# Sheet1.net
KiCad netlist of a schematic drawn in Altium Designer
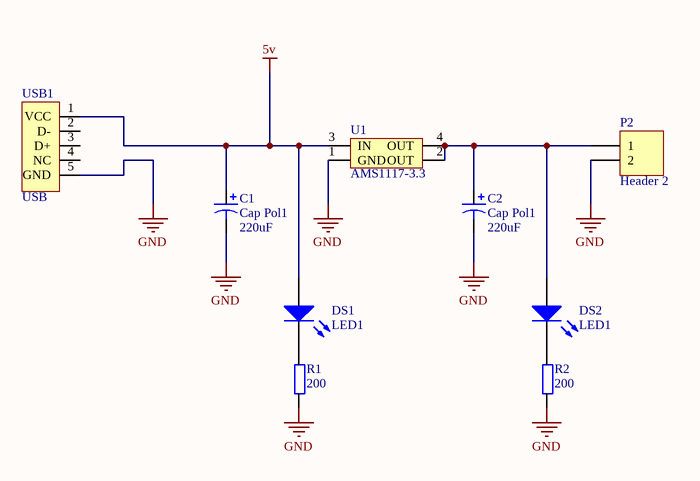
[diagram p0: Sheet1.SchDoc]

(export (version "E")
  (design (tool "Eeschema 10.0.6"))
  (components
    (comp (ref "C1")
      (value "Cap Pol1")
      (footprint "RB015-3:RB.15/.3")
      (description "Polarized Capacitor (Radial)")
      (fields (field (name "ALTIUM_VALUE") "220uF") (field (name "PUBLISHER") "Altium Limited"))
      (libsource (lib "Miscellaneous Devices") (part "Cap Pol1"))
    )
    (comp (ref "C2")
      (value "Cap Pol1")
      (footprint "RB015-3:RB.15/.3")
      (description "Polarized Capacitor (Radial)")
      (fields (field (name "ALTIUM_VALUE") "220uF") (field (name "PUBLISHER") "Altium Limited"))
      (libsource (lib "Miscellaneous Devices") (part "Cap Pol1"))
    )
    (comp (ref "DS1")
      (value "LED1")
      (footprint "LED0805:LED0805")
      (description "Typical RED, GREEN, YELLOW, AMBER GaAs LED")
      (fields (field (name "PUBLISHER") "Altium Limited"))
      (libsource (lib "WarShip V3 STM32103封装库") (part "LED2"))
    )
    (comp (ref "DS2")
      (value "LED1")
      (footprint "LED0805:LED0805")
      (description "Typical RED, GREEN, YELLOW, AMBER GaAs LED")
      (fields (field (name "PUBLISHER") "Altium Limited"))
      (libsource (lib "WarShip V3 STM32103封装库") (part "LED2"))
    )
    (comp (ref "P2")
      (value "Header 2")
      (footprint "HDR1X2")
      (description "Header, 2-Pin")
      (fields (field (name "PUBLISHER") "Altium Limited"))
      (libsource (lib "Miscellaneous Connectors") (part "Header 2"))
    )
    (comp (ref "R1") (value "200") (footprint "0805") (libsource (lib "WarShip V3 STM32103封装库") (part "R")))
    (comp (ref "R2") (value "200") (footprint "0805") (libsource (lib "WarShip V3 STM32103封装库") (part "R")))
    (comp (ref "U1")
      (value "AMS1117-3.3")
      (footprint "AMS1117")
      (libsource (lib "WarShip V3 STM32103封装库") (part "AMS1117"))
    )
    (comp (ref "USB1")
      (value "USB")
      (footprint "DIP-2p")
      (libsource (lib "WarShip V3 STM32103封装库") (part "USB5"))
    )
  )
  (nets
    (net (code "1") (name "5v") (class "Default")
      (node (ref "C1") (pin "1") (pinfunction "1_1") (pintype "passive"))
      (node (ref "DS1") (pin "1") (pinfunction "A_1") (pintype "passive"))
      (node (ref "U1") (pin "3") (pinfunction "IN_3") (pintype "passive"))
      (node (ref "USB1") (pin "1") (pinfunction "VCC_1") (pintype "passive"))
    )
    (net (code "2") (name "GND") (class "Default")
      (node (ref "C1") (pin "2") (pinfunction "2_2") (pintype "passive"))
      (node (ref "C2") (pin "2") (pinfunction "2_2") (pintype "passive"))
      (node (ref "P2") (pin "2") (pinfunction "2_2") (pintype "passive"))
      (node (ref "R1") (pin "1") (pintype "passive"))
      (node (ref "R2") (pin "1") (pintype "passive"))
      (node (ref "U1") (pin "1") (pinfunction "GND_1") (pintype "passive"))
      (node (ref "USB1") (pin "5") (pinfunction "GND_5") (pintype "passive"))
    )
    (net (code "3") (name "Net-(DS1-K)") (class "Default")
      (node (ref "DS1") (pin "2") (pinfunction "K_2") (pintype "passive"))
      (node (ref "R1") (pin "2") (pintype "passive"))
    )
    (net (code "4") (name "Net-(DS2-A)") (class "Default")
      (node (ref "C2") (pin "1") (pinfunction "1_1") (pintype "passive"))
      (node (ref "DS2") (pin "1") (pinfunction "A_1") (pintype "passive"))
      (node (ref "P2") (pin "1") (pinfunction "1_1") (pintype "passive"))
      (node (ref "U1") (pin "2") (pinfunction "OUT_2") (pintype "passive"))
      (node (ref "U1") (pin "4") (pinfunction "OUT_4") (pintype "passive"))
    )
    (net (code "5") (name "Net-(DS2-K)") (class "Default")
      (node (ref "DS2") (pin "2") (pinfunction "K_2") (pintype "passive"))
      (node (ref "R2") (pin "2") (pintype "passive"))
    )
    (net (code "6") (name "unconnected-(USB1-D+-Pad3)") (class "Default")
      (node (ref "USB1") (pin "3") (pinfunction "D+_3") (pintype "passive"))
    )
    (net (code "7") (name "unconnected-(USB1-D--Pad2)") (class "Default")
      (node (ref "USB1") (pin "2") (pinfunction "D-_2") (pintype "passive"))
    )
    (net (code "8") (name "unconnected-(USB1-NC-Pad4)") (class "Default")
      (node (ref "USB1") (pin "4") (pinfunction "NC_4") (pintype "passive"))
    )
  )
)
